# ProDoc_Board1_2025-12-02.net
KiCad netlist of a schematic drawn in EasyEDA Pro
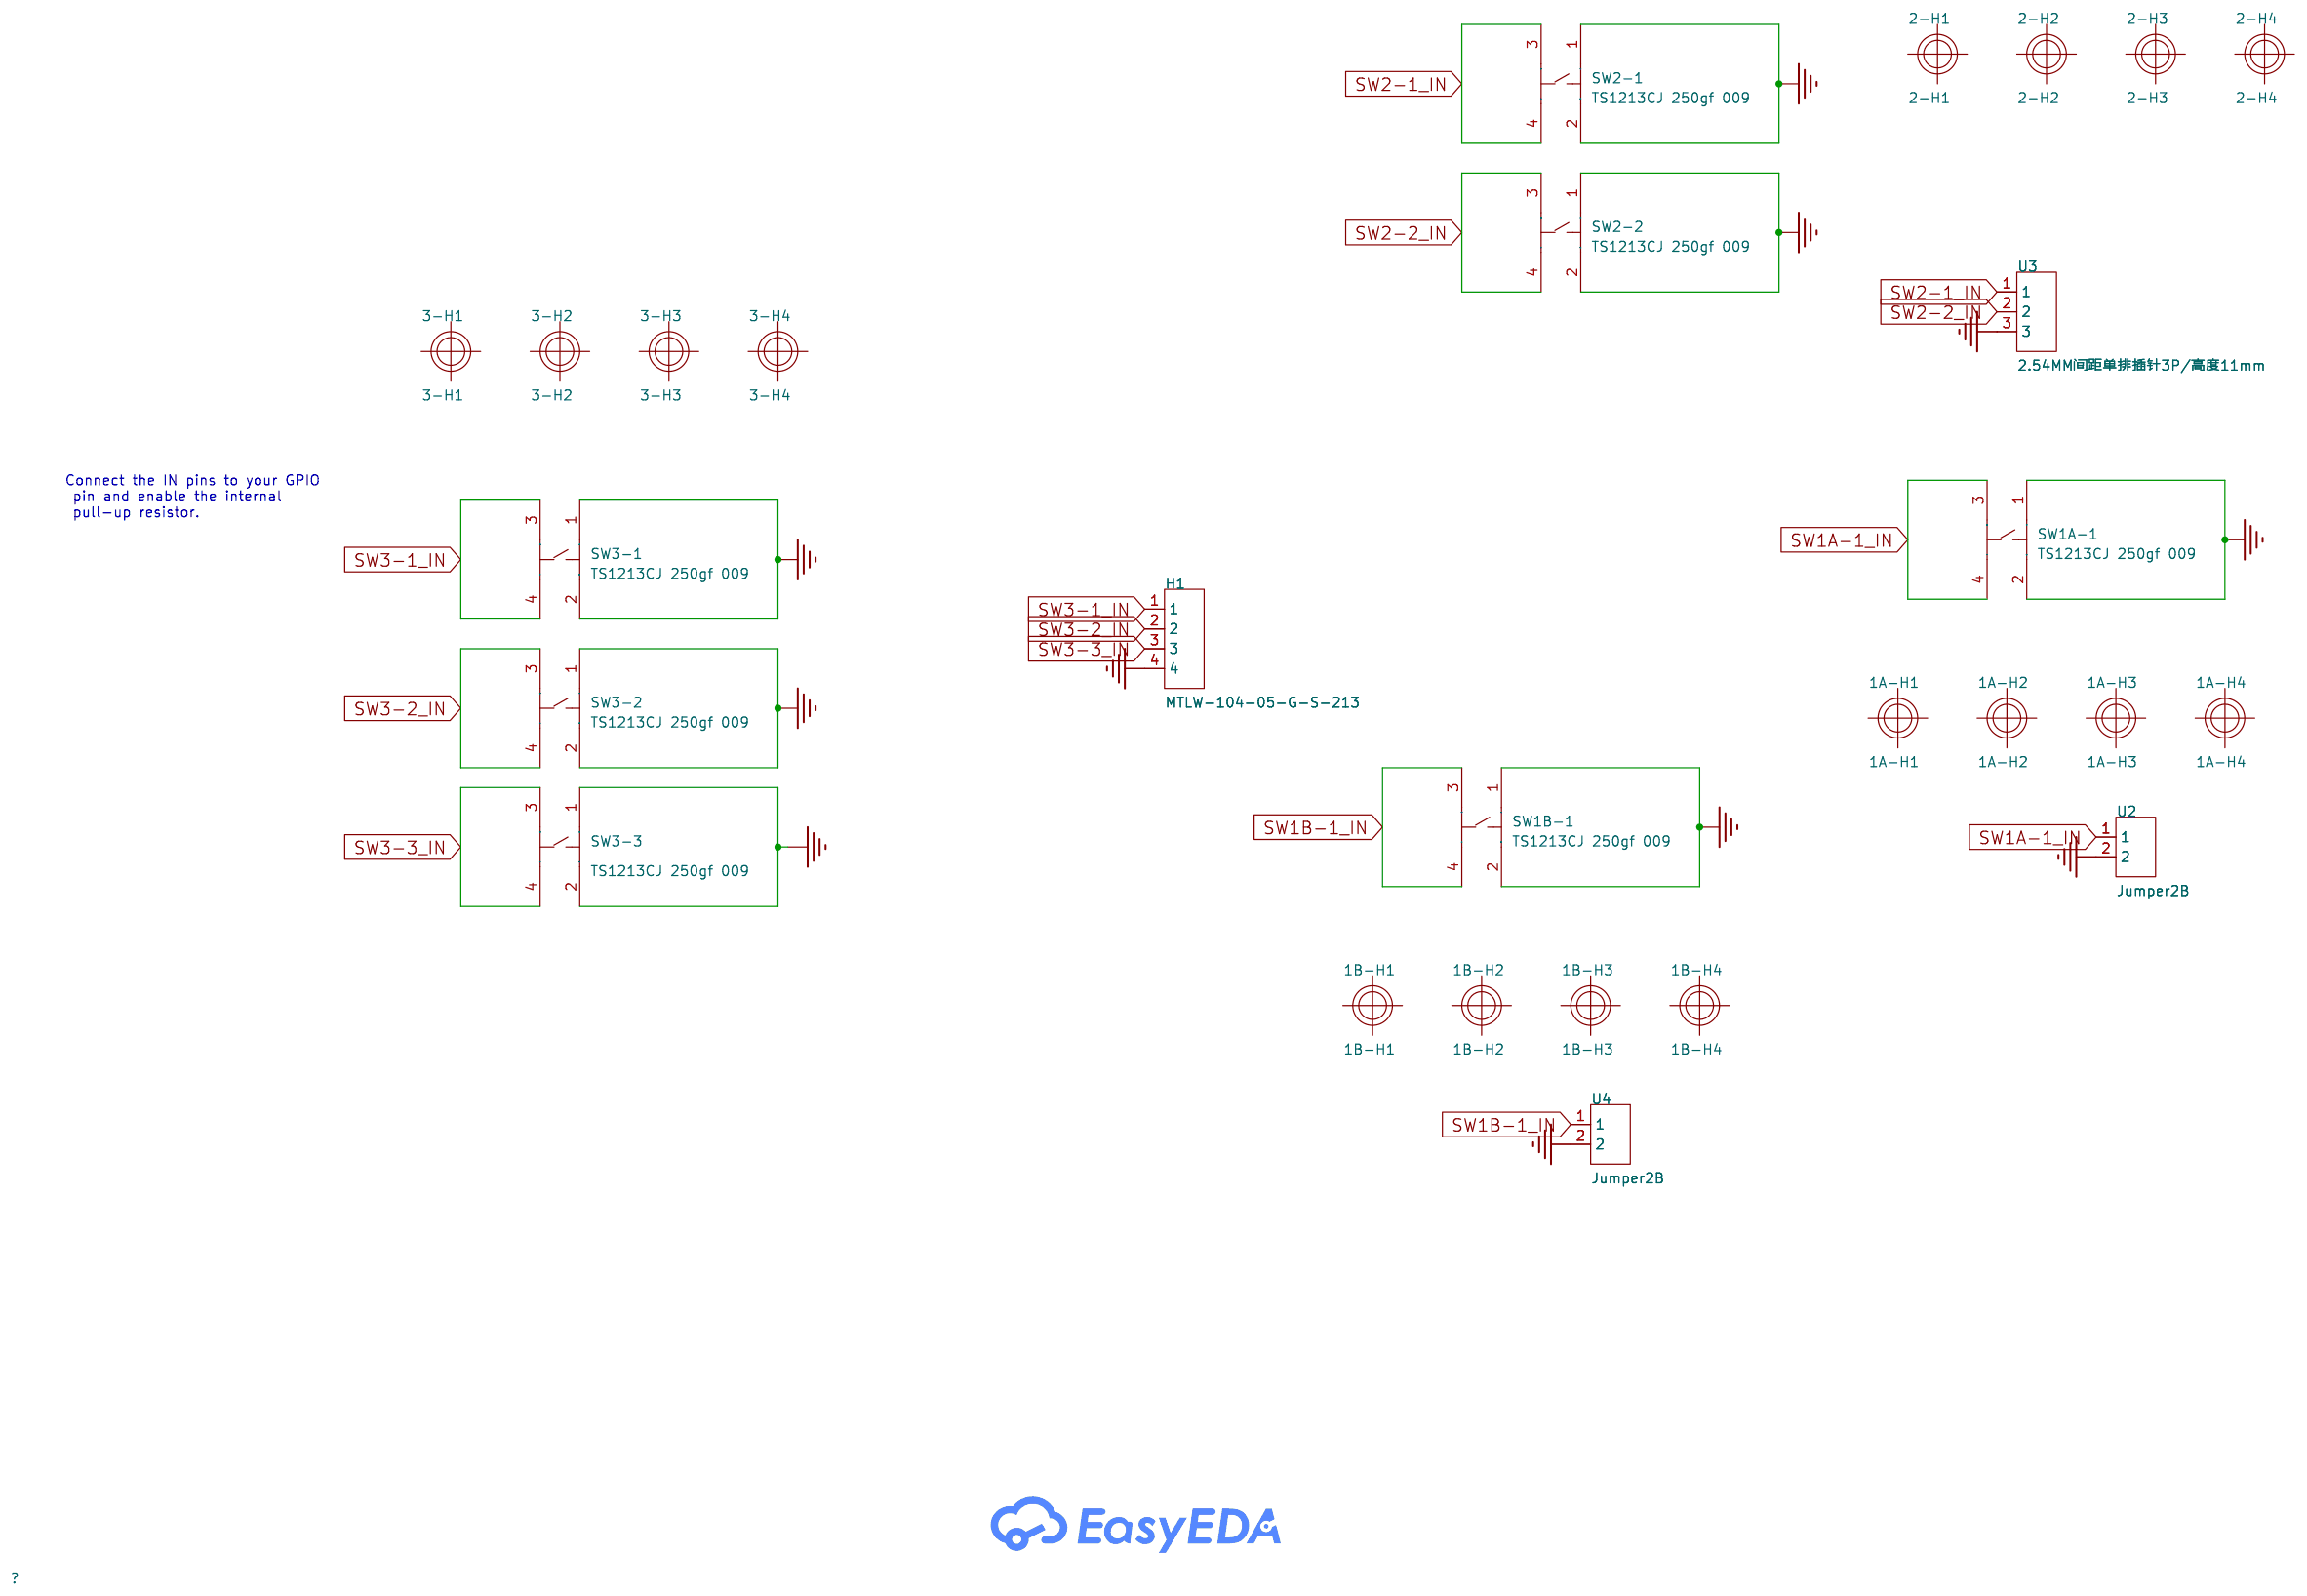
[diagram p0: schematic sheet]

(export (version "E")
  (design (tool "Eeschema 10.0.6"))
  (components
    (comp (ref "1A-H1")
      (value "1A-H1")
      (footprint "easyedapro:MOUNTING_HOLE_3MM")
      (libsource (lib "easyedapro") (part "MOUNTING_HOLE_3MM"))
    )
    (comp (ref "1A-H2")
      (value "1A-H2")
      (footprint "easyedapro:MOUNTING_HOLE_3MM")
      (libsource (lib "easyedapro") (part "MOUNTING_HOLE_3MM"))
    )
    (comp (ref "1A-H3")
      (value "1A-H3")
      (footprint "easyedapro:MOUNTING_HOLE_3MM")
      (libsource (lib "easyedapro") (part "MOUNTING_HOLE_3MM"))
    )
    (comp (ref "1A-H4")
      (value "1A-H4")
      (footprint "easyedapro:MOUNTING_HOLE_3MM")
      (libsource (lib "easyedapro") (part "MOUNTING_HOLE_3MM"))
    )
    (comp (ref "1B-H1")
      (value "1B-H1")
      (footprint "easyedapro:MOUNTING_HOLE_3MM")
      (libsource (lib "easyedapro") (part "MOUNTING_HOLE_3MM"))
    )
    (comp (ref "1B-H2")
      (value "1B-H2")
      (footprint "easyedapro:MOUNTING_HOLE_3MM")
      (libsource (lib "easyedapro") (part "MOUNTING_HOLE_3MM"))
    )
    (comp (ref "1B-H3")
      (value "1B-H3")
      (footprint "easyedapro:MOUNTING_HOLE_3MM")
      (libsource (lib "easyedapro") (part "MOUNTING_HOLE_3MM"))
    )
    (comp (ref "1B-H4")
      (value "1B-H4")
      (footprint "easyedapro:MOUNTING_HOLE_3MM")
      (libsource (lib "easyedapro") (part "MOUNTING_HOLE_3MM"))
    )
    (comp (ref "2-H1")
      (value "2-H1")
      (footprint "easyedapro:MOUNTING_HOLE_3MM")
      (libsource (lib "easyedapro") (part "MOUNTING_HOLE_3MM"))
    )
    (comp (ref "2-H2")
      (value "2-H2")
      (footprint "easyedapro:MOUNTING_HOLE_3MM")
      (libsource (lib "easyedapro") (part "MOUNTING_HOLE_3MM"))
    )
    (comp (ref "2-H3")
      (value "2-H3")
      (footprint "easyedapro:MOUNTING_HOLE_3MM")
      (libsource (lib "easyedapro") (part "MOUNTING_HOLE_3MM"))
    )
    (comp (ref "2-H4")
      (value "2-H4")
      (footprint "easyedapro:MOUNTING_HOLE_3MM")
      (libsource (lib "easyedapro") (part "MOUNTING_HOLE_3MM"))
    )
    (comp (ref "3-H1")
      (value "3-H1")
      (footprint "easyedapro:MOUNTING_HOLE_3MM")
      (libsource (lib "easyedapro") (part "MOUNTING_HOLE_3MM"))
    )
    (comp (ref "3-H2")
      (value "3-H2")
      (footprint "easyedapro:MOUNTING_HOLE_3MM")
      (libsource (lib "easyedapro") (part "MOUNTING_HOLE_3MM"))
    )
    (comp (ref "3-H3")
      (value "3-H3")
      (footprint "easyedapro:MOUNTING_HOLE_3MM")
      (libsource (lib "easyedapro") (part "MOUNTING_HOLE_3MM"))
    )
    (comp (ref "3-H4")
      (value "3-H4")
      (footprint "easyedapro:MOUNTING_HOLE_3MM")
      (libsource (lib "easyedapro") (part "MOUNTING_HOLE_3MM"))
    )
    (comp (ref "H1")
      (value "MTLW-104-05-G-S-213")
      (footprint "easyedapro:HDR-TH_4P-P2.54_MTLW-104-05-G-S-165")
      (fields (field (name "Manufacturer") "SAMTEC"))
      (libsource (lib "easyedapro") (part "MTLW-104-05-G-S-213"))
    )
    (comp (ref "SW1A-1")
      (value "TS1213CJ 250gf 009")
      (footprint "easyedapro:KEY-TH_4P-L12.0-W12.0-P5.00-LS12.5")
      (fields (field (name "Manufacturer") "SHOU HAN(首韩)"))
      (libsource (lib "easyedapro") (part "TS1213CJ 250GF 009"))
    )
    (comp (ref "SW1B-1")
      (value "TS1213CJ 250gf 009")
      (footprint "easyedapro:KEY-TH_4P-L12.0-W12.0-P5.00-LS12.5")
      (fields (field (name "Manufacturer") "SHOU HAN(首韩)"))
      (libsource (lib "easyedapro") (part "TS1213CJ 250GF 009"))
    )
    (comp (ref "SW2-1")
      (value "TS1213CJ 250gf 009")
      (footprint "easyedapro:KEY-TH_4P-L12.0-W12.0-P5.00-LS12.5")
      (fields (field (name "Manufacturer") "SHOU HAN(首韩)"))
      (libsource (lib "easyedapro") (part "TS1213CJ 250GF 009"))
    )
    (comp (ref "SW2-2")
      (value "TS1213CJ 250gf 009")
      (footprint "easyedapro:KEY-TH_4P-L12.0-W12.0-P5.00-LS12.5")
      (fields (field (name "Manufacturer") "SHOU HAN(首韩)"))
      (libsource (lib "easyedapro") (part "TS1213CJ 250GF 009"))
    )
    (comp (ref "SW3-1")
      (value "TS1213CJ 250gf 009")
      (footprint "easyedapro:KEY-TH_4P-L12.0-W12.0-P5.00-LS12.5")
      (fields (field (name "Manufacturer") "SHOU HAN(首韩)"))
      (libsource (lib "easyedapro") (part "TS1213CJ 250GF 009"))
    )
    (comp (ref "SW3-2")
      (value "TS1213CJ 250gf 009")
      (footprint "easyedapro:KEY-TH_4P-L12.0-W12.0-P5.00-LS12.5")
      (fields (field (name "Manufacturer") "SHOU HAN(首韩)"))
      (libsource (lib "easyedapro") (part "TS1213CJ 250GF 009"))
    )
    (comp (ref "SW3-3")
      (value "TS1213CJ 250gf 009")
      (footprint "easyedapro:KEY-TH_4P-L12.0-W12.0-P5.00-LS12.5")
      (fields (field (name "Manufacturer") "SHOU HAN(首韩)"))
      (libsource (lib "easyedapro") (part "TS1213CJ 250GF 009"))
    )
    (comp (ref "U2")
      (value "Jumper2B")
      (footprint "easyedapro:HDR-TH_2P-P2.54-V-M-1")
      (libsource (lib "easyedapro") (part "JUMPER2"))
    )
    (comp (ref "U3")
      (value "2.54MM间距单排插针3P/高度11mm")
      (footprint "easyedapro:HDR-TH_3P-P2.54-V-M")
      (libsource (lib "easyedapro") (part "2.54MM间距单排插针3P/高度11MM"))
    )
    (comp (ref "U4")
      (value "Jumper2B")
      (footprint "easyedapro:HDR-TH_2P-P2.54-V-M-1")
      (libsource (lib "easyedapro") (part "JUMPER2"))
    )
  )
  (nets
    (net (code "1") (name "GND1A") (class "Default")
      (node (ref "SW1A-1") (pin "1") (pinfunction "1_1") (pintype "unspecified"))
      (node (ref "SW1A-1") (pin "2") (pinfunction "2_2") (pintype "unspecified"))
      (node (ref "U2") (pin "2") (pinfunction "2_2") (pintype "unspecified"))
    )
    (net (code "2") (name "GND1B") (class "Default")
      (node (ref "SW1B-1") (pin "1") (pinfunction "1_1") (pintype "unspecified"))
      (node (ref "SW1B-1") (pin "2") (pinfunction "2_2") (pintype "unspecified"))
      (node (ref "U4") (pin "2") (pinfunction "2_2") (pintype "unspecified"))
    )
    (net (code "3") (name "GND2") (class "Default")
      (node (ref "SW2-1") (pin "1") (pinfunction "1_1") (pintype "unspecified"))
      (node (ref "SW2-1") (pin "2") (pinfunction "2_2") (pintype "unspecified"))
      (node (ref "SW2-2") (pin "1") (pinfunction "1_1") (pintype "unspecified"))
      (node (ref "SW2-2") (pin "2") (pinfunction "2_2") (pintype "unspecified"))
      (node (ref "U3") (pin "3") (pinfunction "3_3") (pintype "unspecified"))
    )
    (net (code "4") (name "GND3") (class "Default")
      (node (ref "H1") (pin "4") (pinfunction "4_4") (pintype "unspecified"))
      (node (ref "SW3-1") (pin "1") (pinfunction "1_1") (pintype "unspecified"))
      (node (ref "SW3-1") (pin "2") (pinfunction "2_2") (pintype "unspecified"))
      (node (ref "SW3-2") (pin "1") (pinfunction "1_1") (pintype "unspecified"))
      (node (ref "SW3-2") (pin "2") (pinfunction "2_2") (pintype "unspecified"))
      (node (ref "SW3-3") (pin "1") (pinfunction "1_1") (pintype "unspecified"))
      (node (ref "SW3-3") (pin "2") (pinfunction "2_2") (pintype "unspecified"))
    )
    (net (code "5") (name "SW1A-1_IN") (class "Default")
      (node (ref "SW1A-1") (pin "3") (pinfunction "3_3") (pintype "unspecified"))
      (node (ref "SW1A-1") (pin "4") (pinfunction "4_4") (pintype "unspecified"))
      (node (ref "U2") (pin "1") (pinfunction "1_1") (pintype "unspecified"))
    )
    (net (code "6") (name "SW1B-1_IN") (class "Default")
      (node (ref "SW1B-1") (pin "3") (pinfunction "3_3") (pintype "unspecified"))
      (node (ref "SW1B-1") (pin "4") (pinfunction "4_4") (pintype "unspecified"))
      (node (ref "U4") (pin "1") (pinfunction "1_1") (pintype "unspecified"))
    )
    (net (code "7") (name "SW2-1_IN") (class "Default")
      (node (ref "SW2-1") (pin "3") (pinfunction "3_3") (pintype "unspecified"))
      (node (ref "SW2-1") (pin "4") (pinfunction "4_4") (pintype "unspecified"))
      (node (ref "U3") (pin "1") (pinfunction "1_1") (pintype "unspecified"))
    )
    (net (code "8") (name "SW2-2_IN") (class "Default")
      (node (ref "SW2-2") (pin "3") (pinfunction "3_3") (pintype "unspecified"))
      (node (ref "SW2-2") (pin "4") (pinfunction "4_4") (pintype "unspecified"))
      (node (ref "U3") (pin "2") (pinfunction "2_2") (pintype "unspecified"))
    )
    (net (code "9") (name "SW3-1_IN") (class "Default")
      (node (ref "H1") (pin "1") (pinfunction "1_1") (pintype "unspecified"))
      (node (ref "SW3-1") (pin "3") (pinfunction "3_3") (pintype "unspecified"))
      (node (ref "SW3-1") (pin "4") (pinfunction "4_4") (pintype "unspecified"))
    )
    (net (code "10") (name "SW3-2_IN") (class "Default")
      (node (ref "H1") (pin "2") (pinfunction "2_2") (pintype "unspecified"))
      (node (ref "SW3-2") (pin "3") (pinfunction "3_3") (pintype "unspecified"))
      (node (ref "SW3-2") (pin "4") (pinfunction "4_4") (pintype "unspecified"))
    )
    (net (code "11") (name "SW3-3_IN") (class "Default")
      (node (ref "H1") (pin "3") (pinfunction "3_3") (pintype "unspecified"))
      (node (ref "SW3-3") (pin "3") (pinfunction "3_3") (pintype "unspecified"))
      (node (ref "SW3-3") (pin "4") (pinfunction "4_4") (pintype "unspecified"))
    )
  )
)
